# 28Pins_Schematic.net
KiCad netlist of a schematic drawn in Altium Designer
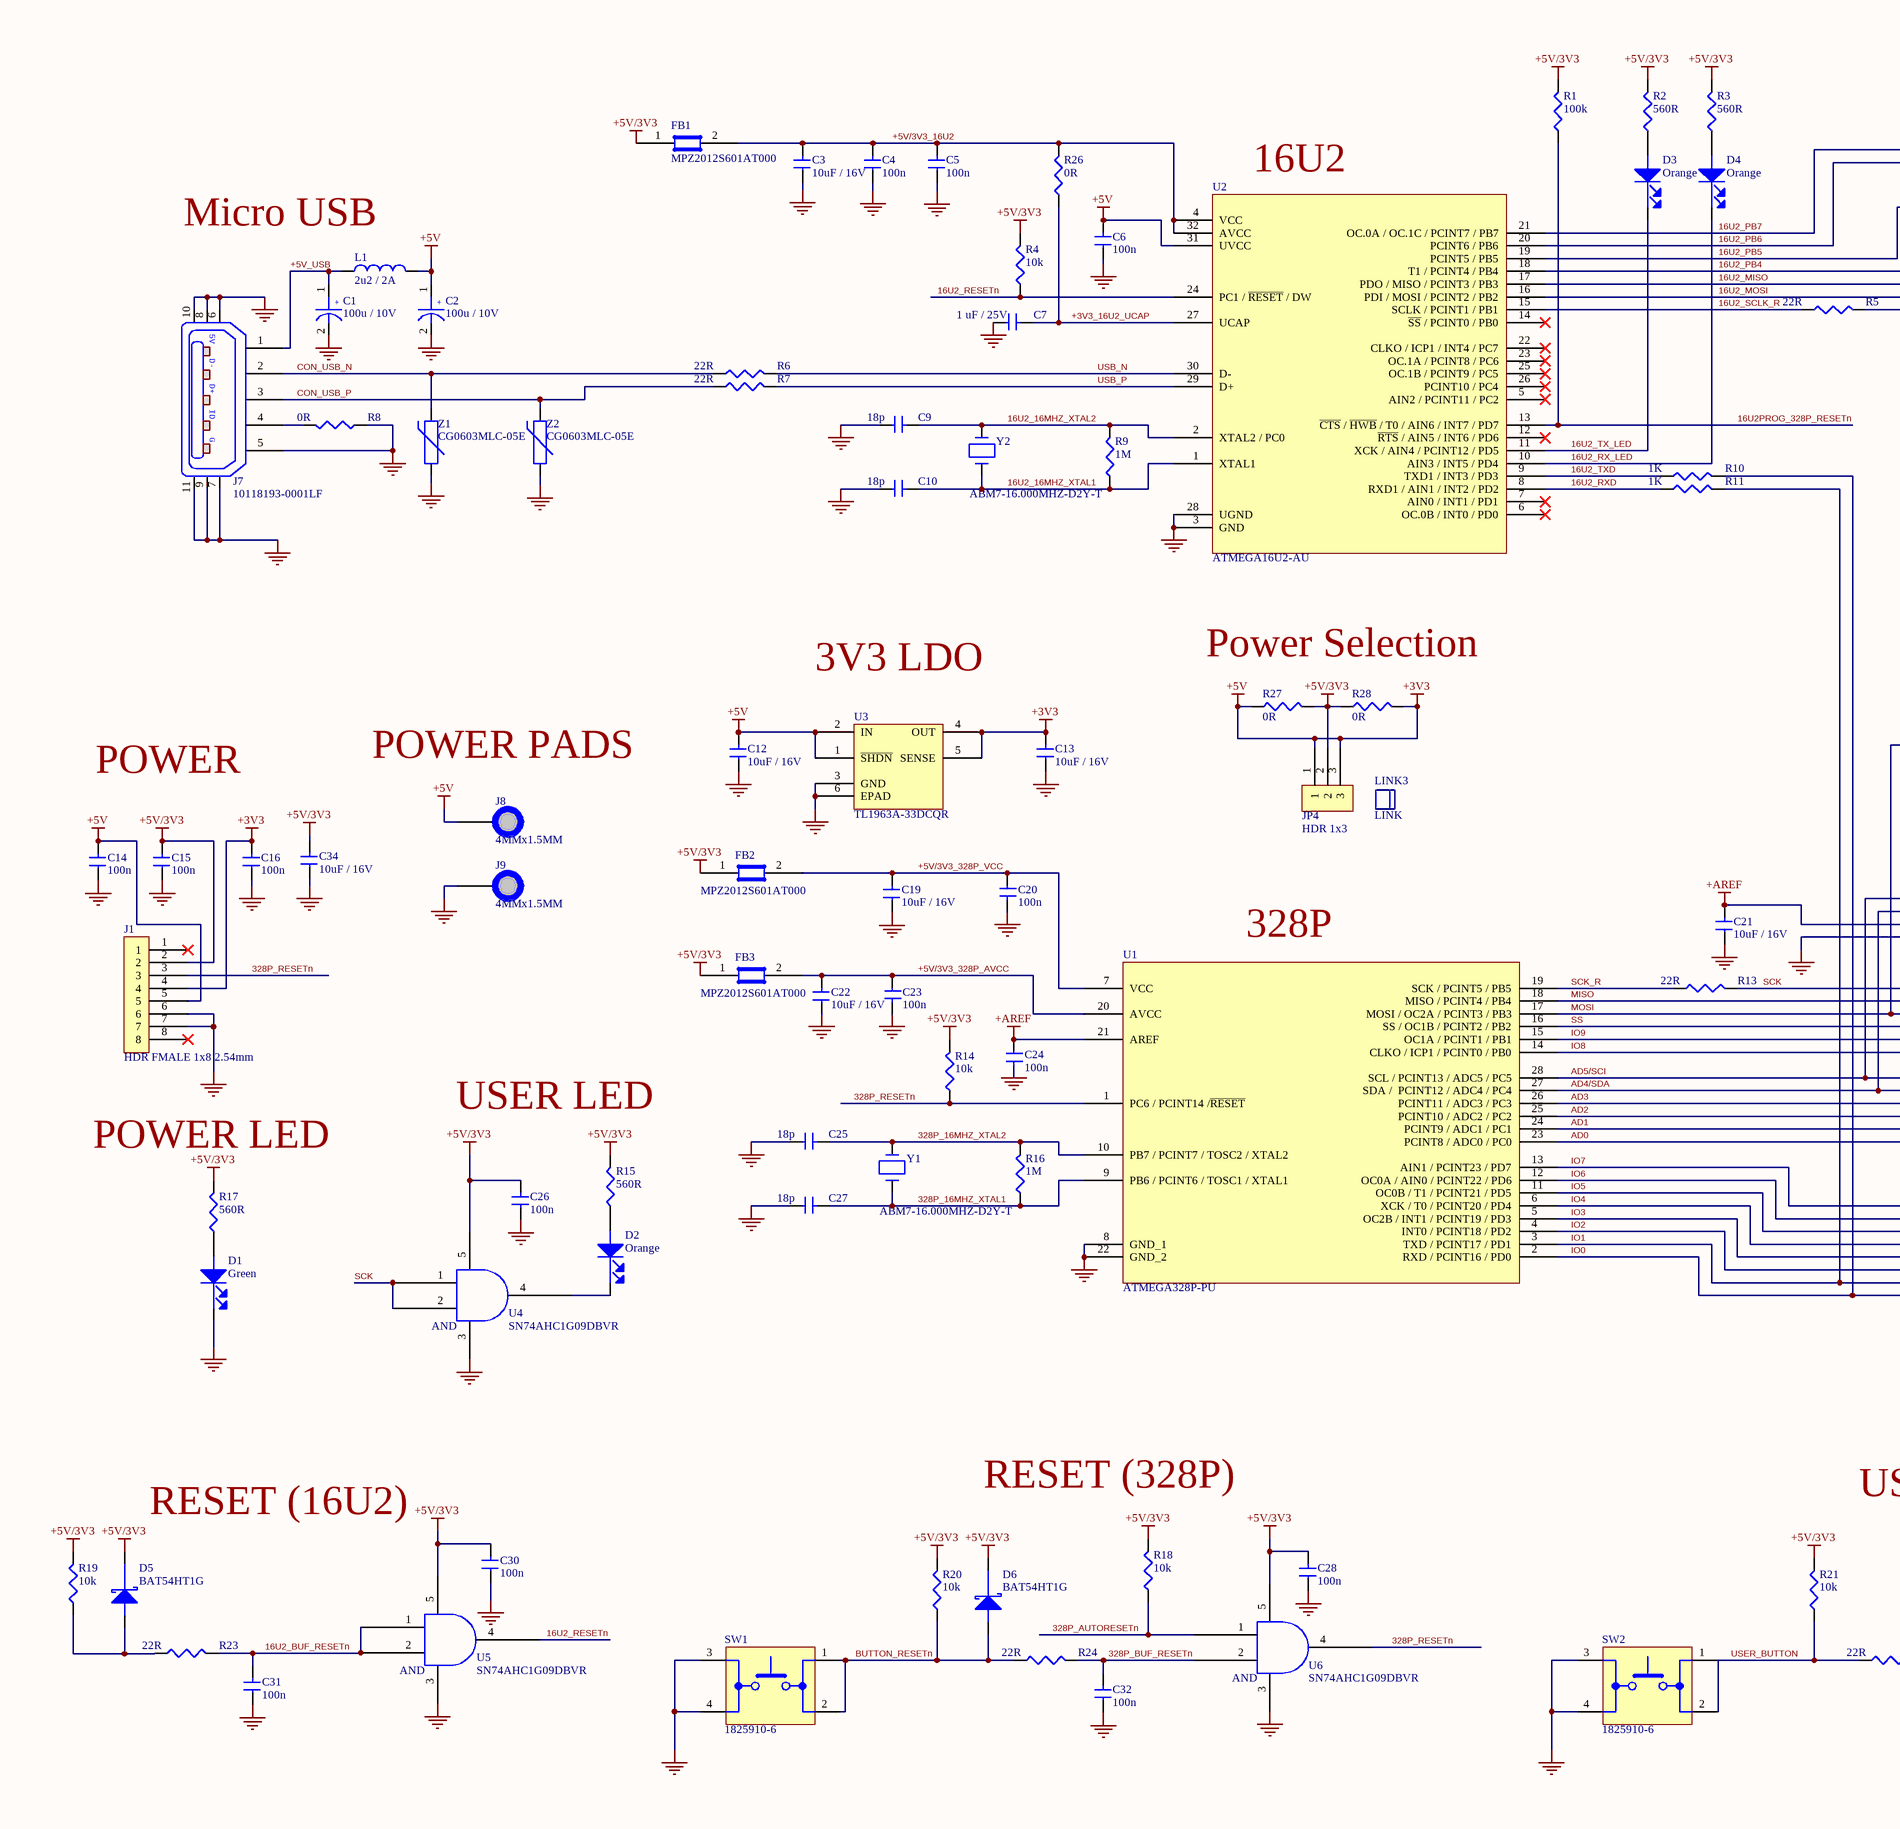
[diagram p0: 28Pins_Schematic.SchDoc, left]
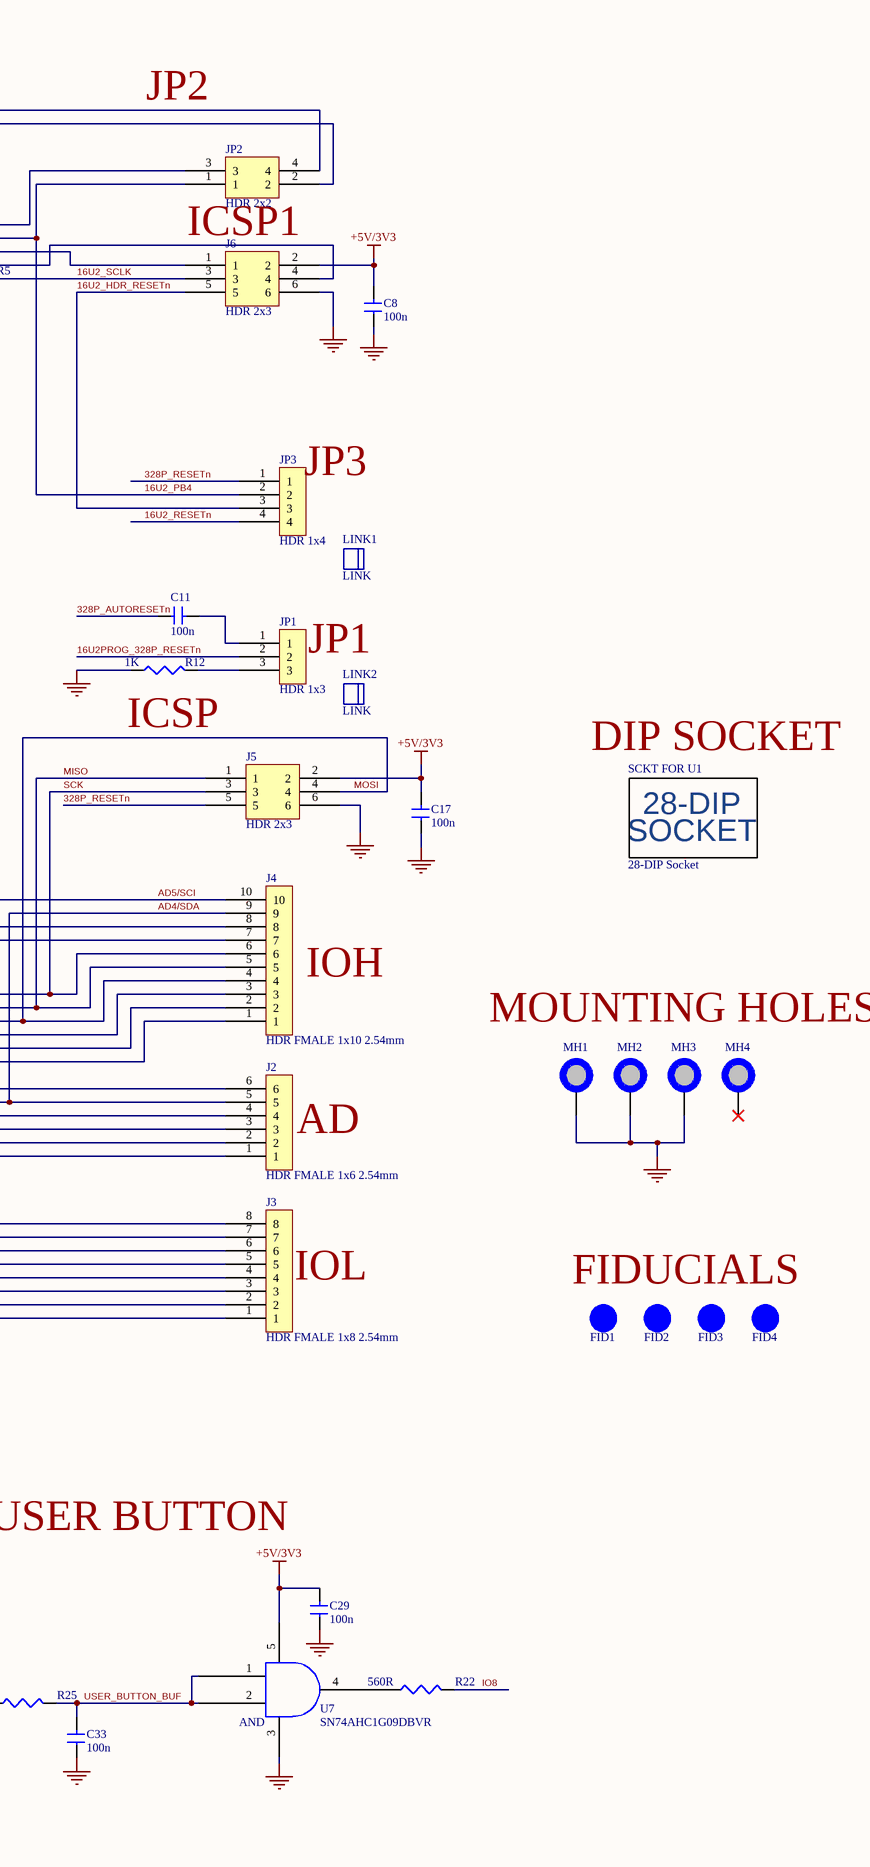
[diagram p1: 28Pins_Schematic.SchDoc, right]

(export (version "E")
  (design (tool "Eeschema 10.0.6"))
  (components
    (comp (ref "C1")
      (value "100u / 10V")
      (footprint "C_ALU_C_SIZE")
      (description "Cap Alum 100uF 10V 20% (5 X 5.4mm) SMD 50mA 1000 hr 85°C T/R")
      (fields
        (field (name "MANUFACTURER") "Panasonic")
        (field (name "MANUFACTURER PART NUMBER") "EEE-1AA101WR")
      )
      (libsource (lib "28Pins_Project_V1I1") (part "EEE-1AA101WR"))
    )
    (comp (ref "C2")
      (value "100u / 10V")
      (footprint "C_ALU_C_SIZE")
      (description "Cap Alum 100uF 10V 20% (5 X 5.4mm) SMD 50mA 1000 hr 85°C T/R")
      (fields
        (field (name "MANUFACTURER") "Panasonic")
        (field (name "MANUFACTURER PART NUMBER") "EEE-1AA101WR")
      )
      (libsource (lib "28Pins_Project_V1I1") (part "EEE-1AA101WR"))
    )
    (comp (ref "C3")
      (value "10uF / 16V")
      (footprint "C0805")
      (fields
        (field (name "MANUFACTURER") "TDK")
        (field (name "MANUFACTURER PART NUMBER") "C2012X5R1C106M125AC")
        (field (name "TOLERANCE") "20%")
      )
      (libsource (lib "28Pins_Project_V1I1") (part "C2012X5R1C106M125AC"))
    )
    (comp (ref "C4")
      (value "100n")
      (footprint "C0805")
      (fields
        (field (name "MANUFACTURER") "TDK")
        (field (name "MANUFACTURER PART NUMBER") "C2012X7R1H104K085AA")
        (field (name "TOLERANCE") "10%")
      )
      (libsource (lib "28Pins_Project_V1I1") (part "C2012X7R1H104K085AA"))
    )
    (comp (ref "C5")
      (value "100n")
      (footprint "C0805")
      (fields
        (field (name "MANUFACTURER") "TDK")
        (field (name "MANUFACTURER PART NUMBER") "C2012X7R1H104K085AA")
        (field (name "TOLERANCE") "10%")
      )
      (libsource (lib "28Pins_Project_V1I1") (part "C2012X7R1H104K085AA"))
    )
    (comp (ref "C6")
      (value "100n")
      (footprint "C0805")
      (fields
        (field (name "MANUFACTURER") "TDK")
        (field (name "MANUFACTURER PART NUMBER") "C2012X7R1H104K085AA")
        (field (name "TOLERANCE") "10%")
      )
      (libsource (lib "28Pins_Project_V1I1") (part "C2012X7R1H104K085AA"))
    )
    (comp (ref "C7")
      (value "1 uF / 25V")
      (footprint "C0805")
      (fields
        (field (name "MANUFACTURER") "TDK")
        (field (name "MANUFACTURER PART NUMBER") "C2012X5R1E105K125AA")
        (field (name "TOLERANCE") "10%")
      )
      (libsource (lib "28Pins_Project_V1I1") (part "C2012X5R1E105K125AA"))
    )
    (comp (ref "C8")
      (value "100n")
      (footprint "C0805")
      (fields
        (field (name "MANUFACTURER") "TDK")
        (field (name "MANUFACTURER PART NUMBER") "C2012X7R1H104K085AA")
        (field (name "TOLERANCE") "10%")
      )
      (libsource (lib "28Pins_Project_V1I1") (part "C2012X7R1H104K085AA"))
    )
    (comp (ref "C9")
      (value "18p")
      (footprint "C0805")
      (description "CAP CER 18PF 50V C0G/NP0 0805")
      (fields
        (field (name "MANUFACTURER") "KEMET")
        (field (name "MANUFACTURER PART NUMBER") "C0805C180J5GACTU")
      )
      (libsource (lib "28Pins_Project_V1I1") (part "C0805C180J5GACTU"))
    )
    (comp (ref "C10")
      (value "18p")
      (footprint "C0805")
      (description "CAP CER 18PF 50V C0G/NP0 0805")
      (fields
        (field (name "MANUFACTURER") "KEMET")
        (field (name "MANUFACTURER PART NUMBER") "C0805C180J5GACTU")
      )
      (libsource (lib "28Pins_Project_V1I1") (part "C0805C180J5GACTU"))
    )
    (comp (ref "C11")
      (value "100n")
      (footprint "C0805")
      (fields
        (field (name "MANUFACTURER") "TDK")
        (field (name "MANUFACTURER PART NUMBER") "C2012X7R1H104K085AA")
        (field (name "TOLERANCE") "10%")
      )
      (libsource (lib "28Pins_Project_V1I1") (part "C2012X7R1H104K085AA"))
    )
    (comp (ref "C12")
      (value "10uF / 16V")
      (footprint "C0805")
      (fields
        (field (name "MANUFACTURER") "TDK")
        (field (name "MANUFACTURER PART NUMBER") "C2012X5R1C106M125AC")
        (field (name "TOLERANCE") "20%")
      )
      (libsource (lib "28Pins_Project_V1I1") (part "C2012X5R1C106M125AC"))
    )
    (comp (ref "C13")
      (value "10uF / 16V")
      (footprint "C0805")
      (fields
        (field (name "MANUFACTURER") "TDK")
        (field (name "MANUFACTURER PART NUMBER") "C2012X5R1C106M125AC")
        (field (name "TOLERANCE") "20%")
      )
      (libsource (lib "28Pins_Project_V1I1") (part "C2012X5R1C106M125AC"))
    )
    (comp (ref "C14")
      (value "100n")
      (footprint "C0805")
      (fields
        (field (name "MANUFACTURER") "TDK")
        (field (name "MANUFACTURER PART NUMBER") "C2012X7R1H104K085AA")
        (field (name "TOLERANCE") "10%")
      )
      (libsource (lib "28Pins_Project_V1I1") (part "C2012X7R1H104K085AA"))
    )
    (comp (ref "C15")
      (value "100n")
      (footprint "C0805")
      (fields
        (field (name "MANUFACTURER") "TDK")
        (field (name "MANUFACTURER PART NUMBER") "C2012X7R1H104K085AA")
        (field (name "TOLERANCE") "10%")
      )
      (libsource (lib "28Pins_Project_V1I1") (part "C2012X7R1H104K085AA"))
    )
    (comp (ref "C16")
      (value "100n")
      (footprint "C0805")
      (fields
        (field (name "MANUFACTURER") "TDK")
        (field (name "MANUFACTURER PART NUMBER") "C2012X7R1H104K085AA")
        (field (name "TOLERANCE") "10%")
      )
      (libsource (lib "28Pins_Project_V1I1") (part "C2012X7R1H104K085AA"))
    )
    (comp (ref "C17")
      (value "100n")
      (footprint "C0805")
      (fields
        (field (name "MANUFACTURER") "TDK")
        (field (name "MANUFACTURER PART NUMBER") "C2012X7R1H104K085AA")
        (field (name "TOLERANCE") "10%")
      )
      (libsource (lib "28Pins_Project_V1I1") (part "C2012X7R1H104K085AA"))
    )
    (comp (ref "C19")
      (value "10uF / 16V")
      (footprint "C0805")
      (fields
        (field (name "MANUFACTURER") "TDK")
        (field (name "MANUFACTURER PART NUMBER") "C2012X5R1C106M125AC")
        (field (name "TOLERANCE") "20%")
      )
      (libsource (lib "28Pins_Project_V1I1") (part "C2012X5R1C106M125AC"))
    )
    (comp (ref "C20")
      (value "100n")
      (footprint "C0805")
      (fields
        (field (name "MANUFACTURER") "TDK")
        (field (name "MANUFACTURER PART NUMBER") "C2012X7R1H104K085AA")
        (field (name "TOLERANCE") "10%")
      )
      (libsource (lib "28Pins_Project_V1I1") (part "C2012X7R1H104K085AA"))
    )
    (comp (ref "C21")
      (value "10uF / 16V")
      (footprint "C0805")
      (fields
        (field (name "MANUFACTURER") "TDK")
        (field (name "MANUFACTURER PART NUMBER") "C2012X5R1C106M125AC")
        (field (name "TOLERANCE") "20%")
      )
      (libsource (lib "28Pins_Project_V1I1") (part "C2012X5R1C106M125AC"))
    )
    (comp (ref "C22")
      (value "10uF / 16V")
      (footprint "C0805")
      (fields
        (field (name "MANUFACTURER") "TDK")
        (field (name "MANUFACTURER PART NUMBER") "C2012X5R1C106M125AC")
        (field (name "TOLERANCE") "20%")
      )
      (libsource (lib "28Pins_Project_V1I1") (part "C2012X5R1C106M125AC"))
    )
    (comp (ref "C23")
      (value "100n")
      (footprint "C0805")
      (fields
        (field (name "MANUFACTURER") "TDK")
        (field (name "MANUFACTURER PART NUMBER") "C2012X7R1H104K085AA")
        (field (name "TOLERANCE") "10%")
      )
      (libsource (lib "28Pins_Project_V1I1") (part "C2012X7R1H104K085AA"))
    )
    (comp (ref "C24")
      (value "100n")
      (footprint "C0805")
      (fields
        (field (name "MANUFACTURER") "TDK")
        (field (name "MANUFACTURER PART NUMBER") "C2012X7R1H104K085AA")
        (field (name "TOLERANCE") "10%")
      )
      (libsource (lib "28Pins_Project_V1I1") (part "C2012X7R1H104K085AA"))
    )
    (comp (ref "C25")
      (value "18p")
      (footprint "C0805")
      (description "CAP CER 18PF 50V C0G/NP0 0805")
      (fields
        (field (name "MANUFACTURER") "KEMET")
        (field (name "MANUFACTURER PART NUMBER") "C0805C180J5GACTU")
      )
      (libsource (lib "28Pins_Project_V1I1") (part "C0805C180J5GACTU"))
    )
    (comp (ref "C26")
      (value "100n")
      (footprint "C0805")
      (fields
        (field (name "MANUFACTURER") "TDK")
        (field (name "MANUFACTURER PART NUMBER") "C2012X7R1H104K085AA")
        (field (name "TOLERANCE") "10%")
      )
      (libsource (lib "28Pins_Project_V1I1") (part "C2012X7R1H104K085AA"))
    )
    (comp (ref "C27")
      (value "18p")
      (footprint "C0805")
      (description "CAP CER 18PF 50V C0G/NP0 0805")
      (fields
        (field (name "MANUFACTURER") "KEMET")
        (field (name "MANUFACTURER PART NUMBER") "C0805C180J5GACTU")
      )
      (libsource (lib "28Pins_Project_V1I1") (part "C0805C180J5GACTU"))
    )
    (comp (ref "C28")
      (value "100n")
      (footprint "C0805")
      (fields
        (field (name "MANUFACTURER") "TDK")
        (field (name "MANUFACTURER PART NUMBER") "C2012X7R1H104K085AA")
        (field (name "TOLERANCE") "10%")
      )
      (libsource (lib "28Pins_Project_V1I1") (part "C2012X7R1H104K085AA"))
    )
    (comp (ref "C29")
      (value "100n")
      (footprint "C0805")
      (fields
        (field (name "MANUFACTURER") "TDK")
        (field (name "MANUFACTURER PART NUMBER") "C2012X7R1H104K085AA")
        (field (name "TOLERANCE") "10%")
      )
      (libsource (lib "28Pins_Project_V1I1") (part "C2012X7R1H104K085AA"))
    )
    (comp (ref "C30")
      (value "100n")
      (footprint "C0805")
      (fields
        (field (name "MANUFACTURER") "TDK")
        (field (name "MANUFACTURER PART NUMBER") "C2012X7R1H104K085AA")
        (field (name "TOLERANCE") "10%")
      )
      (libsource (lib "28Pins_Project_V1I1") (part "C2012X7R1H104K085AA"))
    )
    (comp (ref "C31")
      (value "100n")
      (footprint "C0805")
      (fields
        (field (name "MANUFACTURER") "TDK")
        (field (name "MANUFACTURER PART NUMBER") "C2012X7R1H104K085AA")
        (field (name "TOLERANCE") "10%")
      )
      (libsource (lib "28Pins_Project_V1I1") (part "C2012X7R1H104K085AA"))
    )
    (comp (ref "C32")
      (value "100n")
      (footprint "C0805")
      (fields
        (field (name "MANUFACTURER") "TDK")
        (field (name "MANUFACTURER PART NUMBER") "C2012X7R1H104K085AA")
        (field (name "TOLERANCE") "10%")
      )
      (libsource (lib "28Pins_Project_V1I1") (part "C2012X7R1H104K085AA"))
    )
    (comp (ref "C33")
      (value "100n")
      (footprint "C0805")
      (fields
        (field (name "MANUFACTURER") "TDK")
        (field (name "MANUFACTURER PART NUMBER") "C2012X7R1H104K085AA")
        (field (name "TOLERANCE") "10%")
      )
      (libsource (lib "28Pins_Project_V1I1") (part "C2012X7R1H104K085AA"))
    )
    (comp (ref "C34")
      (value "10uF / 16V")
      (footprint "C0805")
      (fields
        (field (name "MANUFACTURER") "TDK")
        (field (name "MANUFACTURER PART NUMBER") "C2012X5R1C106M125AC")
        (field (name "TOLERANCE") "20%")
      )
      (libsource (lib "28Pins_Project_V1I1") (part "C2012X5R1C106M125AC"))
    )
    (comp (ref "D1")
      (value "Green")
      (footprint "LED_0603")
      (description "LED Green Uni-Color 572nm 2-Pin Chip 0603(1608Metric) T/R")
      (fields
        (field (name "MANUFACTURER") "Osram Opto")
        (field (name "MANUFACTURER PART NUMBER") "LGL29K-G2J1-24-Z")
      )
      (libsource (lib "28Pins_Project_V1I1") (part "LGL29K-G2J1-24-Z"))
    )
    (comp (ref "D2")
      (value "Orange")
      (footprint "LED_0603")
      (description "LED ORANGE SMART OSRAM - LO L29K-H2K1-24-Z - 0603")
      (fields
        (field (name "MANUFACTURER") "Osram Opto")
        (field (name "MANUFACTURER PART NUMBER") "LOL29K-H2K1-24-Z")
      )
      (libsource (lib "28Pins_Project_V1I1") (part "LOL29K-H2K1-24-Z"))
    )
    (comp (ref "D3")
      (value "Orange")
      (footprint "LED_0603")
      (description "LED ORANGE SMART OSRAM - LO L29K-H2K1-24-Z - 0603")
      (fields
        (field (name "MANUFACTURER") "Osram Opto")
        (field (name "MANUFACTURER PART NUMBER") "LOL29K-H2K1-24-Z")
      )
      (libsource (lib "28Pins_Project_V1I1") (part "LOL29K-H2K1-24-Z"))
    )
    (comp (ref "D4")
      (value "Orange")
      (footprint "LED_0603")
      (description "LED ORANGE SMART OSRAM - LO L29K-H2K1-24-Z - 0603")
      (fields
        (field (name "MANUFACTURER") "Osram Opto")
        (field (name "MANUFACTURER PART NUMBER") "LOL29K-H2K1-24-Z")
      )
      (libsource (lib "28Pins_Project_V1I1") (part "LOL29K-H2K1-24-Z"))
    )
    (comp (ref "D5")
      (value "BAT54HT1G")
      (footprint "SOD323")
      (description "Diode Schottky 30V 200 mA, 800 mV, 600 mA, 150 C ;RoHS Compliant: Yes")
      (fields (field (name "MANUFACTURER") "ON Semiconductor / Fairchild"))
      (libsource (lib "28Pins_Project_V1I1") (part "BAT54HT1G"))
    )
    (comp (ref "D6")
      (value "BAT54HT1G")
      (footprint "SOD323")
      (description "Diode Schottky 30V 200 mA, 800 mV, 600 mA, 150 C ;RoHS Compliant: Yes")
      (fields (field (name "MANUFACTURER") "ON Semiconductor / Fairchild"))
      (libsource (lib "28Pins_Project_V1I1") (part "BAT54HT1G"))
    )
    (comp (ref "FB1")
      (value "MPZ2012S601AT000")
      (footprint "C0805")
      (description "FERRITE BEAD 600 OHM 0805 1LN")
      (fields (field (name "MANUFACTURER") "TDK"))
      (libsource (lib "28Pins_Project_V1I1") (part "MPZ2012S601AT000"))
    )
    (comp (ref "FB2")
      (value "MPZ2012S601AT000")
      (footprint "C0805")
      (description "FERRITE BEAD 600 OHM 0805 1LN")
      (fields (field (name "MANUFACTURER") "TDK"))
      (libsource (lib "28Pins_Project_V1I1") (part "MPZ2012S601AT000"))
    )
    (comp (ref "FB3")
      (value "MPZ2012S601AT000")
      (footprint "C0805")
      (description "FERRITE BEAD 600 OHM 0805 1LN")
      (fields (field (name "MANUFACTURER") "TDK"))
      (libsource (lib "28Pins_Project_V1I1") (part "MPZ2012S601AT000"))
    )
    (comp (ref "FID1")
      (value "FID_1MMC")
      (footprint "FID_40X120D")
      (description "Fiducial 40mil Diameter 120mil Mask")
      (libsource (lib "28Pins_Project_V1I1") (part "FID_1MMC"))
    )
    (comp (ref "FID2")
      (value "FID_1MMC")
      (footprint "FID_40X120D")
      (description "Fiducial 40mil Diameter 120mil Mask")
      (libsource (lib "28Pins_Project_V1I1") (part "FID_1MMC"))
    )
    (comp (ref "FID3")
      (value "FID_1MMC")
      (footprint "FID_40X120D")
      (description "Fiducial 40mil Diameter 120mil Mask")
      (libsource (lib "28Pins_Project_V1I1") (part "FID_1MMC"))
    )
    (comp (ref "FID4")
      (value "FID_1MMC")
      (footprint "FID_40X120D")
      (description "Fiducial 40mil Diameter 120mil Mask")
      (libsource (lib "28Pins_Project_V1I1") (part "FID_1MMC"))
    )
    (comp (ref "J1")
      (value "HDR FMALE 1x8 2.54mm")
      (footprint "Hdr_Female_1x8_2.54mm")
      (description "8-WAY 2.54mm (0.1\") Pitch SIL Vertical PC Tail Socket Assembly, selective gold + tin, 8 contacts")
      (fields (field (name "MANUFACTURER") "Harwin") (field (name "MANUFACTURER PART NUMBER") "M20-7820842"))
      (libsource (lib "28Pins_Project_V1I1") (part "M20-7820842"))
    )
    (comp (ref "J2")
      (value "HDR FMALE 1x6 2.54mm")
      (footprint "Hdr_Female_1x6_2.54mm")
      (description "06-WAY SIL VERT SOCKET L/FREE")
      (fields (field (name "MANUFACTURER") "Harwin") (field (name "MANUFACTURER PART NUMBER") "M20-7820646"))
      (libsource (lib "28Pins_Project_V1I1") (part "M20-7820646"))
    )
    (comp (ref "J3")
      (value "HDR FMALE 1x8 2.54mm")
      (footprint "Hdr_Female_1x8_2.54mm")
      (description "2.54mm (0.1\") Pitch SIL Vertical PC Tail Socket Assembly, selective gold + tin, 8 contacts")
      (fields (field (name "MANUFACTURER") "Harwin") (field (name "MANUFACTURER PART NUMBER") "M20-7820842"))
      (libsource (lib "") (part "M20-7820842_1"))
    )
    (comp (ref "J4")
      (value "HDR FMALE 1x10 2.54mm")
      (footprint "Hdr_Female_1x10_2.54mm")
      (fields (field (name "MANUFACTURER") "Harwin") (field (name "MANUFACTURER PART NUMBER") "M20-7821046"))
      (libsource (lib "28Pins_Project_V1I1") (part "M20-7821046"))
    )
    (comp (ref "J5")
      (value "HDR 2x3")
      (footprint "HDR_2x3_2.54MM")
      (description "CONN HEADER 6POS .100 STR 30AU")
      (fields
        (field (name "MANUFACTURER") "Amphenol FCI")
        (field (name "MANUFACTURER PART NUMBER") "67997-106HLF")
      )
      (libsource (lib "28Pins_Project_V1I1") (part "67997-106HLF"))
    )
    (comp (ref "J6")
      (value "HDR 2x3")
      (footprint "HDR_2x3_2.54MM")
      (description "CONN HEADER 6POS .100 STR 30AU")
      (fields
        (field (name "MANUFACTURER") "Amphenol FCI")
        (field (name "MANUFACTURER PART NUMBER") "67997-106HLF")
      )
      (libsource (lib "28Pins_Project_V1I1") (part "67997-106HLF"))
    )
    (comp (ref "J7")
      (value "10118193-0001LF")
      (footprint "10118193")
      (description "CONN USB MICRO B RECPT SMT R/A")
      (fields (field (name "MANUFACTURER") "Amphenol FCI"))
      (libsource (lib "28Pins_Project_V1I1") (part "10118193-0001LF"))
    )
    (comp (ref "J8")
      (value "4MMx1.5MM")
      (footprint "PAD_WITH_HOLE_4MMx1.5MM")
      (description "Pad with a hole 4mm x 1.5mm")
      (libsource (lib "28Pins_Project_V1I1") (part "PAD_WITH_HOLE_4MMx1.5MM"))
    )
    (comp (ref "J9")
      (value "4MMx1.5MM")
      (footprint "PAD_WITH_HOLE_4MMx1.5MM")
      (description "Pad with a hole 4mm x 1.5mm")
      (libsource (lib "28Pins_Project_V1I1") (part "PAD_WITH_HOLE_4MMx1.5MM"))
    )
    (comp (ref "JP1")
      (value "HDR 1x3")
      (footprint "Hdr_1x3_2.54mm")
      (description "HDR 3 POS 2.54mm Conn Unshrouded Header Solder ST Thru-Hole Bulk")
      (fields
        (field (name "MANUFACTURER") "Amphenol FCI")
        (field (name "MANUFACTURER PART NUMBER") "68000-103HLF")
      )
      (libsource (lib "") (part "68000-103HLF_1"))
    )
    (comp (ref "JP2")
      (value "HDR 2x2")
      (footprint "HDR_2x2_2.54MM")
      (description "CONN HEADER 4POS 2.54MM")
      (fields
        (field (name "MANUFACTURER") "Amphenol FCI")
        (field (name "MANUFACTURER PART NUMBER") "68602-204HLF")
      )
      (libsource (lib "28Pins_Project_V1I1") (part "68602-204HLF"))
    )
    (comp (ref "JP3")
      (value "HDR 1x4")
      (footprint "HDR_1x4_2.54MM")
      (description "CONN HEADER 4POS 2.54MM")
      (fields
        (field (name "MANUFACTURER") "Amphenol FCI")
        (field (name "MANUFACTURER PART NUMBER") "68001-204HLF")
      )
      (libsource (lib "28Pins_Project_V1I1") (part "68001-204HLF"))
    )
    (comp (ref "JP4")
      (value "HDR 1x3")
      (footprint "Hdr_1x3_2.54mm")
      (description "Conn HDR 3 POS 2.54mm  Unshrouded Header Solder ST Thru-Hole Bulk")
      (fields
        (field (name "MANUFACTURER") "Amphenol FCI")
        (field (name "MANUFACTURER PART NUMBER") "68000-103HLF")
      )
      (libsource (lib "28Pins_Project_V1I1") (part "68000-103HLF"))
    )
    (comp (ref "L1")
      (value "2u2 / 2A")
      (footprint "C1210_IND")
      (description "FIXED IND 2.2UH 2A 80 MOHM SMD")
      (fields
        (field (name "MANUFACTURER") "KEMET")
        (field (name "MANUFACTURER PART NUMBER") "L1210R2R2MDWIT")
      )
      (libsource (lib "28Pins_Project_V1I1") (part "L1210R2R2MDWIT"))
    )
    (comp (ref "LINK1")
      (value "LINK")
      (description "CONN JUMPER SHORTING .100\" GOLD")
      (fields
        (field (name "MANUFACTURER") "Sullins")
        (field (name "MANUFACTURER PART NUMBER") "QPC02SXGN-RC")
      )
      (libsource (lib "28Pins_Project_V1I1") (part "QPC02SXGN-RC"))
    )
    (comp (ref "LINK2")
      (value "LINK")
      (description "CONN JUMPER SHORTING .100\" GOLD")
      (fields
        (field (name "MANUFACTURER") "Sullins")
        (field (name "MANUFACTURER PART NUMBER") "QPC02SXGN-RC")
      )
      (libsource (lib "28Pins_Project_V1I1") (part "QPC02SXGN-RC"))
    )
    (comp (ref "LINK3")
      (value "LINK")
      (description "CONN JUMPER SHORTING .100\" GOLD")
      (fields
        (field (name "MANUFACTURER") "Sullins")
        (field (name "MANUFACTURER PART NUMBER") "QPC02SXGN-RC")
      )
      (libsource (lib "28Pins_Project_V1I1") (part "QPC02SXGN-RC"))
    )
    (comp (ref "MH1")
      (value "MH_7.4MMC_3.2MMD")
      (footprint "MH_7.4MMD_3_2MMD")
      (description "Mounting Hole 7.4mm Diameter, 3.xmm Drill")
      (libsource (lib "28Pins_Project_V1I1") (part "MH_7.4MMC_3.2"))
    )
    (comp (ref "MH2")
      (value "MH_7.4MMC_3.2MMD")
      (footprint "MH_7.4MMD_3_2MMD")
      (description "Mounting Hole 7.4mm Diameter, 3.xmm Drill")
      (libsource (lib "28Pins_Project_V1I1") (part "MH_7.4MMC_3.2"))
    )
    (comp (ref "MH3")
      (value "MH_7.4MMC_3.2MMD")
      (footprint "MH_7.4MMD_3_2MMD")
      (description "Mounting Hole 7.4mm Diameter, 3.xmm Drill")
      (libsource (lib "28Pins_Project_V1I1") (part "MH_7.4MMC_3.2"))
    )
    (comp (ref "MH4")
      (value "MH_7.4MMNC_3.2MMD")
      (footprint "MH_7.4MMD_3.2MMD_NON_COPPER_NPTH")
      (description "Hole 7.4mm Diameter (Non Copper) 3.2mm Drill NPTH")
      (libsource (lib "28Pins_Project_V1I1") (part "MH_7.4MMNC_3.2MMD"))
    )
    (comp (ref "R1")
      (value "100k")
      (footprint "R0805")
      (description "RES SMD 100K OHM YAGEO RC0805FR-07100KL RES, THICK FILM, 100K, 1%, 0.125W, 0805, REEL")
      (fields
        (field (name "MANUFACTURER") "Yageo")
        (field (name "MANUFACTURER PART NUMBER") "RC0805FR-07100KL")
      )
      (libsource (lib "28Pins_Project_V1I1") (part "RC0805FR-07100KL"))
    )
    (comp (ref "R2")
      (value "560R")
      (footprint "R0805")
      (description "RES SMD 560 OHM Surface Mount Thick Film, RC Series, 125 mW, - 1%, 150 V, 0805 [2012 Metric]")
      (fields
        (field (name "MANUFACTURER") "Yageo")
        (field (name "MANUFACTURER PART NUMBER") "RC0805FR-07560RL")
      )
      (libsource (lib "28Pins_Project_V1I1") (part "RC0805FR-07560RL"))
    )
    (comp (ref "R3")
      (value "560R")
      (footprint "R0805")
      (description "RES SMD 560 OHM Surface Mount Thick Film, RC Series, 125 mW, - 1%, 150 V, 0805 [2012 Metric]")
      (fields
        (field (name "MANUFACTURER") "Yageo")
        (field (name "MANUFACTURER PART NUMBER") "RC0805FR-07560RL")
      )
      (libsource (lib "28Pins_Project_V1I1") (part "RC0805FR-07560RL"))
    )
    (comp (ref "R4")
      (value "10k")
      (description "RES SMD 10K OHM 1% 1/8W 0805")
      (fields
        (field (name "MANUFACTURER") "Yageo")
        (field (name "MANUFACTURER PART NUMBER") "RC0805FR-0710KL")
      )
      (libsource (lib "28Pins_Project_V1I1") (part "RC0805FR-0710KL"))
    )
    (comp (ref "R5")
      (value "22R")
      (footprint "R0805")
      (description "RES SMD 22 OHM 1% 1/8W 0805")
      (fields
        (field (name "MANUFACTURER") "Yageo")
        (field (name "MANUFACTURER PART NUMBER") "RC0805FR-0722RL")
      )
      (libsource (lib "28Pins_Project_V1I1") (part "RC0805FR-0722RL"))
    )
    (comp (ref "R6")
      (value "22R")
      (footprint "R0805")
      (description "RES SMD 22 OHM 1% 1/8W 0805")
      (fields
        (field (name "MANUFACTURER") "Yageo")
        (field (name "MANUFACTURER PART NUMBER") "RC0805FR-0722RL")
      )
      (libsource (lib "28Pins_Project_V1I1") (part "RC0805FR-0722RL"))
    )
    (comp (ref "R7")
      (value "22R")
      (footprint "R0805")
      (description "RES SMD 22 OHM 1% 1/8W 0805")
      (fields
        (field (name "MANUFACTURER") "Yageo")
        (field (name "MANUFACTURER PART NUMBER") "RC0805FR-0722RL")
      )
      (libsource (lib "28Pins_Project_V1I1") (part "RC0805FR-0722RL"))
    )
    (comp (ref "R8")
      (value "0R")
      (footprint "R0805")
      (fields
        (field (name "MANUFACTURER") "Yageo")
        (field (name "MANUFACTURER PART NUMBER") "RC0805JR-070RL")
        (field (name "TOLERANCE") "5%")
      )
      (libsource (lib "28Pins_Project_V1I1") (part "RC0805JR-070RL"))
    )
    (comp (ref "R9")
      (value "1M")
      (footprint "R0805")
      (description "RES SMD 1M OHM 1% 1/8W 0805")
      (fields
        (field (name "MANUFACTURER") "Yageo")
        (field (name "MANUFACTURER PART NUMBER") "RC0805FR-071ML")
      )
      (libsource (lib "28Pins_Project_V1I1") (part "RC0805FR-071ML"))
    )
    (comp (ref "R10")
      (value "1K")
      (footprint "R0805")
      (fields
        (field (name "MANUFACTURER") "Yageo")
        (field (name "MANUFACTURER PART NUMBER") "RC0805FR-071KL")
        (field (name "TOLERANCE") "1%")
      )
      (libsource (lib "28Pins_Project_V1I1") (part "RC0805FR-071KL"))
    )
    (comp (ref "R11")
      (value "1K")
      (footprint "R0805")
      (fields
        (field (name "MANUFACTURER") "Yageo")
        (field (name "MANUFACTURER PART NUMBER") "RC0805FR-071KL")
        (field (name "TOLERANCE") "1%")
      )
      (libsource (lib "28Pins_Project_V1I1") (part "RC0805FR-071KL"))
    )
    (comp (ref "R12")
      (value "1K")
      (footprint "R0805")
      (fields
        (field (name "MANUFACTURER") "Yageo")
        (field (name "MANUFACTURER PART NUMBER") "RC0805FR-071KL")
        (field (name "TOLERANCE") "1%")
      )
      (libsource (lib "28Pins_Project_V1I1") (part "RC0805FR-071KL"))
    )
    (comp (ref "R13")
      (value "22R")
      (footprint "R0805")
      (description "RES SMD 22 OHM 1% 1/8W 0805")
      (fields
        (field (name "MANUFACTURER") "Yageo")
        (field (name "MANUFACTURER PART NUMBER") "RC0805FR-0722RL")
      )
      (libsource (lib "28Pins_Project_V1I1") (part "RC0805FR-0722RL"))
    )
    (comp (ref "R14")
      (value "10k")
      (description "RES SMD 10K OHM 1% 1/8W 0805")
      (fields
        (field (name "MANUFACTURER") "Yageo")
        (field (name "MANUFACTURER PART NUMBER") "RC0805FR-0710KL")
      )
      (libsource (lib "28Pins_Project_V1I1") (part "RC0805FR-0710KL"))
    )
    (comp (ref "R15")
      (value "560R")
      (footprint "R0805")
      (description "RES SMD 560 OHM Surface Mount Thick Film, RC Series, 125 mW, - 1%, 150 V, 0805 [2012 Metric]")
      (fields
        (field (name "MANUFACTURER") "Yageo")
        (field (name "MANUFACTURER PART NUMBER") "RC0805FR-07560RL")
      )
      (libsource (lib "28Pins_Project_V1I1") (part "RC0805FR-07560RL"))
    )
    (comp (ref "R16")
      (value "1M")
      (footprint "R0805")
      (description "RES SMD 1M OHM 1% 1/8W 0805")
      (fields
        (field (name "MANUFACTURER") "Yageo")
        (field (name "MANUFACTURER PART NUMBER") "RC0805FR-071ML")
      )
      (libsource (lib "28Pins_Project_V1I1") (part "RC0805FR-071ML"))
    )
    (comp (ref "R17")
      (value "560R")
      (footprint "R0805")
      (description "RES SMD 560 OHM Surface Mount Thick Film, RC Series, 125 mW, - 1%, 150 V, 0805 [2012 Metric]")
      (fields
        (field (name "MANUFACTURER") "Yageo")
        (field (name "MANUFACTURER PART NUMBER") "RC0805FR-07560RL")
      )
      (libsource (lib "28Pins_Project_V1I1") (part "RC0805FR-07560RL"))
    )
    (comp (ref "R18")
      (value "10k")
      (description "RES SMD 10K OHM 1% 1/8W 0805")
      (fields
        (field (name "MANUFACTURER") "Yageo")
        (field (name "MANUFACTURER PART NUMBER") "RC0805FR-0710KL")
      )
      (libsource (lib "28Pins_Project_V1I1") (part "RC0805FR-0710KL"))
    )
    (comp (ref "R19")
      (value "10k")
      (description "RES SMD 10K OHM 1% 1/8W 0805")
      (fields
        (field (name "MANUFACTURER") "Yageo")
        (field (name "MANUFACTURER PART NUMBER") "RC0805FR-0710KL")
      )
      (libsource (lib "28Pins_Project_V1I1") (part "RC0805FR-0710KL"))
    )
    (comp (ref "R20")
      (value "10k")
      (description "RES SMD 10K OHM 1% 1/8W 0805")
      (fields
        (field (name "MANUFACTURER") "Yageo")
        (field (name "MANUFACTURER PART NUMBER") "RC0805FR-0710KL")
      )
      (libsource (lib "28Pins_Project_V1I1") (part "RC0805FR-0710KL"))
    )
    (comp (ref "R21")
      (value "10k")
      (description "RES SMD 10K OHM 1% 1/8W 0805")
      (fields
        (field (name "MANUFACTURER") "Yageo")
        (field (name "MANUFACTURER PART NUMBER") "RC0805FR-0710KL")
      )
      (libsource (lib "28Pins_Project_V1I1") (part "RC0805FR-0710KL"))
    )
    (comp (ref "R22")
      (value "560R")
      (footprint "R0805")
      (description "RES SMD 560 OHM Surface Mount Thick Film, RC Series, 125 mW, - 1%, 150 V, 0805 [2012 Metric]")
      (fields
        (field (name "MANUFACTURER") "Yageo")
        (field (name "MANUFACTURER PART NUMBER") "RC0805FR-07560RL")
      )
      (libsource (lib "28Pins_Project_V1I1") (part "RC0805FR-07560RL"))
    )
    (comp (ref "R23")
      (value "22R")
      (footprint "R0805")
      (description "RES SMD 22 OHM 1% 1/8W 0805")
      (fields
        (field (name "MANUFACTURER") "Yageo")
        (field (name "MANUFACTURER PART NUMBER") "RC0805FR-0722RL")
      )
      (libsource (lib "28Pins_Project_V1I1") (part "RC0805FR-0722RL"))
    )
    (comp (ref "R24")
      (value "22R")
      (footprint "R0805")
      (description "RES SMD 22 OHM 1% 1/8W 0805")
      (fields
        (field (name "MANUFACTURER") "Yageo")
        (field (name "MANUFACTURER PART NUMBER") "RC0805FR-0722RL")
      )
      (libsource (lib "28Pins_Project_V1I1") (part "RC0805FR-0722RL"))
    )
    (comp (ref "R25")
      (value "22R")
      (footprint "R0805")
      (description "RES SMD 22 OHM 1% 1/8W 0805")
      (fields
        (field (name "MANUFACTURER") "Yageo")
        (field (name "MANUFACTURER PART NUMBER") "RC0805FR-0722RL")
      )
      (libsource (lib "28Pins_Project_V1I1") (part "RC0805FR-0722RL"))
    )
    (comp (ref "R26")
      (value "0R")
      (footprint "R0805")
      (fields
        (field (name "MANUFACTURER") "Yageo")
        (field (name "MANUFACTURER PART NUMBER") "RC0805JR-070RL")
        (field (name "TOLERANCE") "5%")
      )
      (libsource (lib "28Pins_Project_V1I1") (part "RC0805JR-070RL"))
    )
    (comp (ref "R27")
      (value "0R")
      (footprint "R0805")
      (fields
        (field (name "MANUFACTURER") "Yageo")
        (field (name "MANUFACTURER PART NUMBER") "RC0805JR-070RL")
        (field (name "TOLERANCE") "5%")
      )
      (libsource (lib "28Pins_Project_V1I1") (part "RC0805JR-070RL"))
    )
    (comp (ref "R28")
      (value "0R")
      (footprint "R0805")
      (fields
        (field (name "MANUFACTURER") "Yageo")
        (field (name "MANUFACTURER PART NUMBER") "RC0805JR-070RL")
        (field (name "TOLERANCE") "5%")
      )
      (libsource (lib "28Pins_Project_V1I1") (part "RC0805JR-070RL"))
    )
    (comp (ref "SCKT FOR U1")
      (value "28-DIP Socket")
      (footprint "28_DIP_7.62mm_SOCKET")
      (description "CONN IC DIP SOCKET 28POS TIN")
      (fields (field (name "MANUFACTURER") "3M") (field (name "MANUFACTURER PART NUMBER") "4828-3004-CP"))
      (libsource (lib "28Pins_Project_V1I1") (part "4828-3004-CP"))
    )
    (comp (ref "SW1")
      (value "1825910-6")
      (footprint "1825910-6")
      (description "SWITCH TACTILE SPST-NO 0.05A 24V")
      (fields (field (name "MANUFACTURER") "TE Connectivity Alcoswitch"))
      (libsource (lib "28Pins_Project_V1I1") (part "1825910-6"))
    )
    (comp (ref "SW2")
      (value "1825910-6")
      (footprint "1825910-6")
      (description "SWITCH TACTILE SPST-NO 0.05A 24V")
      (fields (field (name "MANUFACTURER") "TE Connectivity Alcoswitch"))
      (libsource (lib "28Pins_Project_V1I1") (part "1825910-6"))
    )
    (comp (ref "U1")
      (value "ATMEGA328P-PU")
      (footprint "28_DIP_7.62mm - duplicate")
      (description "ATMEGA328P-PU; 8 bit Microcontroller AVR 20MHz 1; 32kb Flash; 2kb RAM; I2C SPI 2")
      (fields (field (name "MANUFACTURER") "Microchip / Atmel"))
      (libsource (lib "28Pins_Project_V1I1") (part "ATMEGA328P-PU"))
    )
    (comp (ref "U2")
      (value "ATMEGA16U2-AU")
      (footprint "TQFP32")
      (description "MICROCHIP - ATMEGA16U2-AU - MCU, 8BIT, MEGAAVR, 16MHZ, TQFP-32")
      (fields (field (name "MANUFACTURER") "Microchip / Atmel"))
      (libsource (lib "28Pins_Project_V1I1") (part "ATMEGA16U2-AU"))
    )
    (comp (ref "U3")
      (value "TL1963A-33DCQR")
      (footprint "DCQ (R-PDSO-G6)")
      (description "IC REG LINEAR 3.3V 1.5A SOT223-6")
      (fields (field (name "MANUFACTURER") "Texas Instruments"))
      (libsource (lib "28Pins_Project_V1I1") (part "TL1963A-33DCQR"))
    )
    (comp (ref "U4")
      (value "SN74AHC1G09DBVR")
      (footprint "DBV_SOT_23_5")
      (description "AND Gate - TEXAS INSTRUMENTS - SN74AHC1G09DBVR, 74AHC1G09, 2 Input, 2 V to 5.5 V, SOT-23-5")
      (fields (field (name "MANUFACTURER") "Texas Instruments"))
      (libsource (lib "28Pins_Project_V1I1") (part "SN74AHC1G09DBVR"))
    )
    (comp (ref "U5")
      (value "SN74AHC1G09DBVR")
      (footprint "DBV_SOT_23_5")
      (description "AND Gate - TEXAS INSTRUMENTS - SN74AHC1G09DBVR, 74AHC1G09, 2 Input, 2 V to 5.5 V, SOT-23-5")
      (fields (field (name "MANUFACTURER") "Texas Instruments"))
      (libsource (lib "28Pins_Project_V1I1") (part "SN74AHC1G09DBVR"))
    )
    (comp (ref "U6")
      (value "SN74AHC1G09DBVR")
      (footprint "DBV_SOT_23_5")
      (description "AND Gate - TEXAS INSTRUMENTS - SN74AHC1G09DBVR, 74AHC1G09, 2 Input, 2 V to 5.5 V, SOT-23-5")
      (fields (field (name "MANUFACTURER") "Texas Instruments"))
      (libsource (lib "28Pins_Project_V1I1") (part "SN74AHC1G09DBVR"))
    )
    (comp (ref "U7")
      (value "SN74AHC1G09DBVR")
      (footprint "DBV_SOT_23_5")
      (description "AND Gate - TEXAS INSTRUMENTS - SN74AHC1G09DBVR, 74AHC1G09, 2 Input, 2 V to 5.5 V, SOT-23-5")
      (fields (field (name "MANUFACTURER") "Texas Instruments"))
      (libsource (lib "28Pins_Project_V1I1") (part "SN74AHC1G09DBVR"))
    )
    (comp (ref "Y1")
      (value "ABM7-16.000MHZ-D2Y-T")
      (footprint "ABM7_v1_1_BIG")
      (description "CRYSTAL 16.0000MHZ 18PF SMD")
      (fields (field (name "MANUFACTURER") "Abracon") (field (name "TOLERANCE") "20ppm"))
      (libsource (lib "28Pins_Project_V1I1") (part "ABM7-16.000MHZ-D2Y-T"))
    )
    (comp (ref "Y2")
      (value "ABM7-16.000MHZ-D2Y-T")
      (footprint "ABM7_v1_1_BIG")
      (description "CRYSTAL 16.0000MHZ 18PF SMD")
      (fields (field (name "MANUFACTURER") "Abracon") (field (name "TOLERANCE") "20ppm"))
      (libsource (lib "28Pins_Project_V1I1") (part "ABM7-16.000MHZ-D2Y-T"))
    )
    (comp (ref "Z1")
      (value "CG0603MLC-05E")
      (footprint "R0603")
      (description "VARISTOR 0603")
      (fields (field (name "MANUFACTURER") "Bourns") (field (name "VOLTAGE") "5V"))
      (libsource (lib "28Pins_Project_V1I1") (part "CG0603MLC-05E"))
    )
    (comp (ref "Z2")
      (value "CG0603MLC-05E")
      (footprint "R0603")
      (description "VARISTOR 0603")
      (fields (field (name "MANUFACTURER") "Bourns") (field (name "VOLTAGE") "5V"))
      (libsource (lib "28Pins_Project_V1I1") (part "CG0603MLC-05E"))
    )
  )
  (nets
    (net (code "1") (name "+3V3") (class "Default")
      (node (ref "C12") (pin "2") (pinfunction "2_2") (pintype "passive"))
      (node (ref "C13") (pin "2") (pinfunction "2_2") (pintype "passive"))
      (node (ref "C14") (pin "2") (pinfunction "2_2") (pintype "passive"))
      (node (ref "C16") (pin "2") (pinfunction "2_2") (pintype "passive"))
      (node (ref "C2") (pin "1") (pinfunction "1_1") (pintype "passive"))
      (node (ref "C6") (pin "2") (pinfunction "2_2") (pintype "passive"))
      (node (ref "J1") (pin "4") (pinfunction "4_4") (pintype "passive"))
      (node (ref "J1") (pin "5") (pinfunction "5_5") (pintype "passive"))
      (node (ref "J8") (pin "1") (pinfunction "1_1") (pintype "passive"))
      (node (ref "JP4") (pin "1") (pinfunction "1_1") (pintype "passive"))
      (node (ref "JP4") (pin "3") (pinfunction "3_3") (pintype "passive"))
      (node (ref "L1") (pin "2") (pinfunction "2_2") (pintype "passive"))
      (node (ref "R27") (pin "1") (pinfunction "1_1") (pintype "passive"))
      (node (ref "R28") (pin "2") (pinfunction "2_2") (pintype "passive"))
      (node (ref "U2") (pin "31") (pinfunction "UVCC_31") (pintype "passive"))
      (node (ref "U3") (pin "1") (pinfunction "~{SHDN}_1") (pintype "passive"))
      (node (ref "U3") (pin "2") (pinfunction "IN_2") (pintype "passive"))
      (node (ref "U3") (pin "4") (pinfunction "OUT_4") (pintype "passive"))
      (node (ref "U3") (pin "5") (pinfunction "SENSE_5") (pintype "passive"))
    )
    (net (code "2") (name "+5V{slash}3V3") (class "Default")
      (node (ref "C15") (pin "2") (pinfunction "2_2") (pintype "passive"))
      (node (ref "C17") (pin "2") (pinfunction "2_2") (pintype "passive"))
      (node (ref "C26") (pin "2") (pinfunction "2_2") (pintype "passive"))
      (node (ref "C28") (pin "2") (pinfunction "2_2") (pintype "passive"))
      (node (ref "C29") (pin "2") (pinfunction "2_2") (pintype "passive"))
      (node (ref "C30") (pin "2") (pinfunction "2_2") (pintype "passive"))
      (node (ref "C34") (pin "2") (pinfunction "2_2") (pintype "passive"))
      (node (ref "C8") (pin "2") (pinfunction "2_2") (pintype "passive"))
      (node (ref "D5") (pin "1") (pinfunction "Cathode_1") (pintype "passive"))
      (node (ref "D6") (pin "1") (pinfunction "Cathode_1") (pintype "passive"))
      (node (ref "FB1") (pin "1") (pinfunction "1_1") (pintype "passive"))
      (node (ref "FB2") (pin "1") (pinfunction "1_1") (pintype "passive"))
      (node (ref "FB3") (pin "1") (pinfunction "1_1") (pintype "passive"))
      (node (ref "J1") (pin "2") (pinfunction "2_2") (pintype "passive"))
      (node (ref "J5") (pin "2") (pinfunction "2_2") (pintype "passive"))
      (node (ref "J6") (pin "2") (pinfunction "2_2") (pintype "passive"))
      (node (ref "JP4") (pin "2") (pinfunction "2_2") (pintype "passive"))
      (node (ref "R1") (pin "2") (pinfunction "2_2") (pintype "passive"))
      (node (ref "R14") (pin "2") (pinfunction "2_2") (pintype "passive"))
      (node (ref "R15") (pin "2") (pinfunction "2_2") (pintype "passive"))
      (node (ref "R17") (pin "2") (pinfunction "2_2") (pintype "passive"))
      (node (ref "R18") (pin "2") (pinfunction "2_2") (pintype "passive"))
      (node (ref "R19") (pin "2") (pinfunction "2_2") (pintype "passive"))
      (node (ref "R2") (pin "2") (pinfunction "2_2") (pintype "passive"))
      (node (ref "R20") (pin "2") (pinfunction "2_2") (pintype "passive"))
      (node (ref "R21") (pin "2") (pinfunction "2_2") (pintype "passive"))
      (node (ref "R27") (pin "2") (pinfunction "2_2") (pintype "passive"))
      (node (ref "R28") (pin "1") (pinfunction "1_1") (pintype "passive"))
      (node (ref "R3") (pin "2") (pinfunction "2_2") (pintype "passive"))
      (node (ref "R4") (pin "2") (pinfunction "2_2") (pintype "passive"))
      (node (ref "U4") (pin "5") (pinfunction "5_5") (pintype "passive"))
      (node (ref "U5") (pin "5") (pinfunction "5_5") (pintype "passive"))
      (node (ref "U6") (pin "5") (pinfunction "5_5") (pintype "passive"))
      (node (ref "U7") (pin "5") (pinfunction "5_5") (pintype "passive"))
    )
    (net (code "3") (name "+AREF") (class "Default")
      (node (ref "C21") (pin "2") (pinfunction "2_2") (pintype "passive"))
      (node (ref "C24") (pin "1") (pinfunction "1_1") (pintype "passive"))
      (node (ref "J4") (pin "8") (pinfunction "8_8") (pintype "passive"))
      (node (ref "U1") (pin "21") (pinfunction "AREF_21") (pintype "passive"))
    )
    (net (code "4") (name "/+3V3_16U2_UCAP") (class "Default")
      (node (ref "C7") (pin "2") (pinfunction "2_2") (pintype "passive"))
      (node (ref "R26") (pin "1") (pinfunction "1_1") (pintype "passive"))
      (node (ref "U2") (pin "27") (pinfunction "UCAP_27") (pintype "passive"))
    )
    (net (code "5") (name "/+5V_USB") (class "Default")
      (node (ref "C1") (pin "1") (pinfunction "1_1") (pintype "passive"))
      (node (ref "J7") (pin "1") (pinfunction "1_1") (pintype "passive"))
      (node (ref "L1") (pin "1") (pinfunction "1_1") (pintype "passive"))
    )
    (net (code "6") (name "/+5V{slash}3V3_16U2") (class "Default")
      (node (ref "C3") (pin "2") (pinfunction "2_2") (pintype "passive"))
      (node (ref "C4") (pin "2") (pinfunction "2_2") (pintype "passive"))
      (node (ref "C5") (pin "2") (pinfunction "2_2") (pintype "passive"))
      (node (ref "FB1") (pin "2") (pinfunction "2_2") (pintype "passive"))
      (node (ref "R26") (pin "2") (pinfunction "2_2") (pintype "passive"))
      (node (ref "U2") (pin "32") (pinfunction "AVCC_32") (pintype "passive"))
      (node (ref "U2") (pin "4") (pinfunction "VCC_4") (pintype "passive"))
    )
    (net (code "7") (name "/+5V{slash}3V3_328P_AVCC") (class "Default")
      (node (ref "C22") (pin "2") (pinfunction "2_2") (pintype "passive"))
      (node (ref "C23") (pin "1") (pinfunction "1_1") (pintype "passive"))
      (node (ref "FB3") (pin "2") (pinfunction "2_2") (pintype "passive"))
      (node (ref "U1") (pin "20") (pinfunction "AVCC_20") (pintype "passive"))
    )
    (net (code "8") (name "/+5V{slash}3V3_328P_VCC") (class "Default")
      (node (ref "C19") (pin "2") (pinfunction "2_2") (pintype "passive"))
      (node (ref "C20") (pin "1") (pinfunction "1_1") (pintype "passive"))
      (node (ref "FB2") (pin "2") (pinfunction "2_2") (pintype "passive"))
      (node (ref "U1") (pin "7") (pinfunction "VCC_7") (pintype "passive"))
    )
    (net (code "9") (name "/16U2PROG_328P_RESETn") (class "Default")
      (node (ref "JP1") (pin "2") (pinfunction "2_2") (pintype "passive"))
      (node (ref "R1") (pin "1") (pinfunction "1_1") (pintype "passive"))
      (node (ref "U2") (pin "13") (pinfunction "~{CTS}_/_~{HWB}_/_T0_/_AIN6_/_INT7_/_PD7_13") (pintype "passive"))
    )
    (net (code "10") (name "/16U2_16MHZ_XTAL1") (class "Default")
      (node (ref "C10") (pin "2") (pinfunction "2_2") (pintype "passive"))
      (node (ref "R9") (pin "1") (pinfunction "1_1") (pintype "passive"))
      (node (ref "U2") (pin "1") (pinfunction "XTAL1_1") (pintype "passive"))
      (node (ref "Y2") (pin "1") (pinfunction "1_1") (pintype "passive"))
    )
    (net (code "11") (name "/16U2_16MHZ_XTAL2") (class "Default")
      (node (ref "C9") (pin "2") (pinfunction "2_2") (pintype "passive"))
      (node (ref "R9") (pin "2") (pinfunction "2_2") (pintype "passive"))
      (node (ref "U2") (pin "2") (pinfunction "XTAL2_/_PC0_2") (pintype "passive"))
      (node (ref "Y2") (pin "2") (pinfunction "2_2") (pintype "passive"))
    )
    (net (code "12") (name "/16U2_BUF_RESETn") (class "Default")
      (node (ref "C31") (pin "2") (pinfunction "2_2") (pintype "passive"))
      (node (ref "R23") (pin "2") (pinfunction "2_2") (pintype "passive"))
      (node (ref "U5") (pin "1") (pinfunction "1_1") (pintype "passive"))
      (node (ref "U5") (pin "2") (pinfunction "2_2") (pintype "passive"))
    )
    (net (code "13") (name "/16U2_HDR_RESETn") (class "Default")
      (node (ref "J6") (pin "5") (pinfunction "5_5") (pintype "passive"))
      (node (ref "JP3") (pin "3") (pinfunction "3_3") (pintype "passive"))
    )
    (net (code "14") (name "/16U2_MISO") (class "Default")
      (node (ref "J6") (pin "1") (pinfunction "1_1") (pintype "passive"))
      (node (ref "U2") (pin "17") (pinfunction "PDO_/_MISO_/_PCINT3_/_PB3_17") (pintype "passive"))
    )
    (net (code "15") (name "/16U2_MOSI") (class "Default")
      (node (ref "J6") (pin "4") (pinfunction "4_4") (pintype "passive"))
      (node (ref "U2") (pin "16") (pinfunction "PDI_/_MOSI_/_PCINT2_/_PB2_16") (pintype "passive"))
    )
    (net (code "16") (name "/16U2_PB4") (class "Default")
      (node (ref "JP2") (pin "1") (pinfunction "1_1") (pintype "passive"))
      (node (ref "JP3") (pin "2") (pinfunction "2_2") (pintype "passive"))
      (node (ref "U2") (pin "18") (pinfunction "T1_/_PCINT4_/_PB4_18") (pintype "passive"))
    )
    (net (code "17") (name "/16U2_PB5") (class "Default")
      (node (ref "JP2") (pin "3") (pinfunction "3_3") (pintype "passive"))
      (node (ref "U2") (pin "19") (pinfunction "PCINT5_/_PB5_19") (pintype "passive"))
    )
    (net (code "18") (name "/16U2_PB6") (class "Default")
      (node (ref "JP2") (pin "2") (pinfunction "2_2") (pintype "passive"))
      (node (ref "U2") (pin "20") (pinfunction "PCINT6_/_PB6_20") (pintype "passive"))
    )
    (net (code "19") (name "/16U2_PB7") (class "Default")
      (node (ref "JP2") (pin "4") (pinfunction "4_4") (pintype "passive"))
      (node (ref "U2") (pin "21") (pinfunction "OC.0A_/_OC.1C_/_PCINT7_/_PB7_21") (pintype "passive"))
    )
    (net (code "20") (name "/16U2_RESETn") (class "Default")
      (node (ref "JP3") (pin "4") (pinfunction "4_4") (pintype "passive"))
      (node (ref "R4") (pin "1") (pinfunction "1_1") (pintype "passive"))
      (node (ref "U2") (pin "24") (pinfunction "PC1_/_~{RESET}_/_DW_24") (pintype "passive"))
      (node (ref "U5") (pin "4") (pinfunction "4_4") (pintype "passive"))
    )
    (net (code "21") (name "/16U2_RXD") (class "Default")
      (node (ref "R11") (pin "1") (pinfunction "1_1") (pintype "passive"))
      (node (ref "U2") (pin "8") (pinfunction "RXD1_/_AIN1_/_INT2_/_PD2_8") (pintype "passive"))
    )
    (net (code "22") (name "/16U2_RX_LED") (class "Default")
      (node (ref "D4") (pin "1") (pinfunction "Cathode_1") (pintype "passive"))
      (node (ref "U2") (pin "10") (pinfunction "AIN3_/_INT5_/_PD4_10") (pintype "passive"))
    )
    (net (code "23") (name "/16U2_SCLK") (class "Default")
      (node (ref "J6") (pin "3") (pinfunction "3_3") (pintype "passive"))
      (node (ref "R5") (pin "2") (pinfunction "2_2") (pintype "passive"))
    )
    (net (code "24") (name "/16U2_SCLK_R") (class "Default")
      (node (ref "R5") (pin "1") (pinfunction "1_1") (pintype "passive"))
      (node (ref "U2") (pin "15") (pinfunction "SCLK_/_PCINT1_/_PB1_15") (pintype "passive"))
    )
    (net (code "25") (name "/16U2_TXD") (class "Default")
      (node (ref "R10") (pin "1") (pinfunction "1_1") (pintype "passive"))
      (node (ref "U2") (pin "9") (pinfunction "TXD1_/_INT3_/_PD3_9") (pintype "passive"))
    )
    (net (code "26") (name "/16U2_TX_LED") (class "Default")
      (node (ref "D3") (pin "1") (pinfunction "Cathode_1") (pintype "passive"))
      (node (ref "U2") (pin "11") (pinfunction "XCK_/_AIN4_/_PCINT12_/_PD5_11") (pintype "passive"))
    )
    (net (code "27") (name "/328P_16MHZ_XTAL1") (class "Default")
      (node (ref "C27") (pin "2") (pinfunction "2_2") (pintype "passive"))
      (node (ref "R16") (pin "1") (pinfunction "1_1") (pintype "passive"))
      (node (ref "U1") (pin "9") (pinfunction "PB6_/_PCINT6_/_TOSC1_/_XTAL1_9") (pintype "passive"))
      (node (ref "Y1") (pin "1") (pinfunction "1_1") (pintype "passive"))
    )
    (net (code "28") (name "/328P_16MHZ_XTAL2") (class "Default")
      (node (ref "C25") (pin "2") (pinfunction "2_2") (pintype "passive"))
      (node (ref "R16") (pin "2") (pinfunction "2_2") (pintype "passive"))
      (node (ref "U1") (pin "10") (pinfunction "PB7_/_PCINT7_/_TOSC2_/_XTAL2_10") (pintype "passive"))
      (node (ref "Y1") (pin "2") (pinfunction "2_2") (pintype "passive"))
    )
    (net (code "29") (name "/328P_AUTORESETn") (class "Default")
      (node (ref "C11") (pin "1") (pinfunction "1_1") (pintype "passive"))
      (node (ref "R18") (pin "1") (pinfunction "1_1") (pintype "passive"))
      (node (ref "U6") (pin "1") (pinfunction "1_1") (pintype "passive"))
    )
    (net (code "30") (name "/328P_BUF_RESETn") (class "Default")
      (node (ref "C32") (pin "2") (pinfunction "2_2") (pintype "passive"))
      (node (ref "R24") (pin "2") (pinfunction "2_2") (pintype "passive"))
      (node (ref "U6") (pin "2") (pinfunction "2_2") (pintype "passive"))
    )
    (net (code "31") (name "/328P_RESETn") (class "Default")
      (node (ref "J1") (pin "3") (pinfunction "3_3") (pintype "passive"))
      (node (ref "J5") (pin "5") (pinfunction "5_5") (pintype "passive"))
      (node (ref "JP3") (pin "1") (pinfunction "1_1") (pintype "passive"))
      (node (ref "R14") (pin "1") (pinfunction "1_1") (pintype "passive"))
      (node (ref "U1") (pin "1") (pinfunction "PC6_/_PCINT14_/~{RESET}_1") (pintype "passive"))
      (node (ref "U6") (pin "4") (pinfunction "4_4") (pintype "passive"))
    )
    (net (code "32") (name "/AD0") (class "Default")
      (node (ref "J2") (pin "1") (pinfunction "1_1") (pintype "passive"))
      (node (ref "U1") (pin "23") (pinfunction "PCINT8_/_ADC0_/_PC0_23") (pintype "passive"))
    )
    (net (code "33") (name "/AD1") (class "Default")
      (node (ref "J2") (pin "2") (pinfunction "2_2") (pintype "passive"))
      (node (ref "U1") (pin "24") (pinfunction "PCINT9_/_ADC1_/_PC1_24") (pintype "passive"))
    )
    (net (code "34") (name "/AD2") (class "Default")
      (node (ref "J2") (pin "3") (pinfunction "3_3") (pintype "passive"))
      (node (ref "U1") (pin "25") (pinfunction "PCINT10_/_ADC2_/_PC2_25") (pintype "passive"))
    )
    (net (code "35") (name "/AD3") (class "Default")
      (node (ref "J2") (pin "4") (pinfunction "4_4") (pintype "passive"))
      (node (ref "U1") (pin "26") (pinfunction "PCINT11_/_ADC3_/_PC3_26") (pintype "passive"))
    )
    (net (code "36") (name "/AD4{slash}SDA") (class "Default")
      (node (ref "J2") (pin "5") (pinfunction "5_5") (pintype "passive"))
      (node (ref "J4") (pin "9") (pinfunction "9_9") (pintype "passive"))
      (node (ref "U1") (pin "27") (pinfunction "SDA_/__PCINT12_/_ADC4_/_PC4_27") (pintype "passive"))
    )
    (net (code "37") (name "/AD5{slash}SCI") (class "Default")
      (node (ref "J2") (pin "6") (pinfunction "6_6") (pintype "passive"))
      (node (ref "J4") (pin "10") (pinfunction "10_10") (pintype "passive"))
      (node (ref "U1") (pin "28") (pinfunction "SCL_/_PCINT13_/_ADC5_/_PC5_28") (pintype "passive"))
    )
    (net (code "38") (name "/BUTTON_RESETn") (class "Default")
      (node (ref "D6") (pin "2") (pinfunction "Anode_2") (pintype "passive"))
      (node (ref "R20") (pin "1") (pinfunction "1_1") (pintype "passive"))
      (node (ref "R24") (pin "1") (pinfunction "1_1") (pintype "passive"))
    )
    (net (code "39") (name "/CON_USB_N") (class "Default")
      (node (ref "J7") (pin "2") (pinfunction "2_2") (pintype "passive"))
      (node (ref "R6") (pin "1") (pinfunction "1_1") (pintype "passive"))
      (node (ref "Z1") (pin "2") (pinfunction "2_2") (pintype "passive"))
    )
    (net (code "40") (name "/CON_USB_P") (class "Default")
      (node (ref "J7") (pin "3") (pinfunction "3_3") (pintype "passive"))
      (node (ref "R7") (pin "1") (pinfunction "1_1") (pintype "passive"))
      (node (ref "Z2") (pin "2") (pinfunction "2_2") (pintype "passive"))
    )
    (net (code "41") (name "/IO0") (class "Default")
      (node (ref "J3") (pin "1") (pinfunction "1_1") (pintype "passive"))
      (node (ref "R10") (pin "2") (pinfunction "2_2") (pintype "passive"))
      (node (ref "U1") (pin "2") (pinfunction "RXD_/_PCINT16_/_PD0_2") (pintype "passive"))
    )
    (net (code "42") (name "/IO1") (class "Default")
      (node (ref "J3") (pin "2") (pinfunction "2_2") (pintype "passive"))
      (node (ref "R11") (pin "2") (pinfunction "2_2") (pintype "passive"))
      (node (ref "U1") (pin "3") (pinfunction "TXD_/_PCINT17_/_PD1_3") (pintype "passive"))
    )
    (net (code "43") (name "/IO2") (class "Default")
      (node (ref "J3") (pin "3") (pinfunction "3_3") (pintype "passive"))
      (node (ref "U1") (pin "4") (pinfunction "INT0_/_PCINT18_/_PD2_4") (pintype "passive"))
    )
    (net (code "44") (name "/IO3") (class "Default")
      (node (ref "J3") (pin "4") (pinfunction "4_4") (pintype "passive"))
      (node (ref "U1") (pin "5") (pinfunction "OC2B_/_INT1_/_PCINT19_/_PD3_5") (pintype "passive"))
    )
    (net (code "45") (name "/IO4") (class "Default")
      (node (ref "J3") (pin "5") (pinfunction "5_5") (pintype "passive"))
      (node (ref "U1") (pin "6") (pinfunction "XCK_/_T0_/_PCINT20_/_PD4_6") (pintype "passive"))
    )
    (net (code "46") (name "/IO5") (class "Default")
      (node (ref "J3") (pin "6") (pinfunction "6_6") (pintype "passive"))
      (node (ref "U1") (pin "11") (pinfunction "OC0B_/_T1_/_PCINT21_/_PD5_11") (pintype "passive"))
    )
    (net (code "47") (name "/IO6") (class "Default")
      (node (ref "J3") (pin "7") (pinfunction "7_7") (pintype "passive"))
      (node (ref "U1") (pin "12") (pinfunction "OC0A_/_AIN0_/_PCINT22_/_PD6_12") (pintype "passive"))
    )
    (net (code "48") (name "/IO7") (class "Default")
      (node (ref "J3") (pin "8") (pinfunction "8_8") (pintype "passive"))
      (node (ref "U1") (pin "13") (pinfunction "AIN1_/_PCINT23_/_PD7_13") (pintype "passive"))
    )
    (net (code "49") (name "/IO8") (class "Default")
      (node (ref "J4") (pin "1") (pinfunction "1_1") (pintype "passive"))
      (node (ref "R22") (pin "2") (pinfunction "2_2") (pintype "passive"))
      (node (ref "U1") (pin "14") (pinfunction "CLKO_/_ICP1_/_PCINT0_/_PB0_14") (pintype "passive"))
    )
    (net (code "50") (name "/IO9") (class "Default")
      (node (ref "J4") (pin "2") (pinfunction "2_2") (pintype "passive"))
      (node (ref "U1") (pin "15") (pinfunction "OC1A_/_PCINT1_/_PB1_15") (pintype "passive"))
    )
    (net (code "51") (name "/MISO") (class "Default")
      (node (ref "J4") (pin "5") (pinfunction "5_5") (pintype "passive"))
      (node (ref "J5") (pin "1") (pinfunction "1_1") (pintype "passive"))
      (node (ref "U1") (pin "18") (pinfunction "MISO_/_PCINT4_/_PB4_18") (pintype "passive"))
    )
    (net (code "52") (name "/MOSI") (class "Default")
      (node (ref "J4") (pin "4") (pinfunction "4_4") (pintype "passive"))
      (node (ref "J5") (pin "4") (pinfunction "4_4") (pintype "passive"))
      (node (ref "U1") (pin "17") (pinfunction "MOSI_/_OC2A_/_PCINT3_/_PB3_17") (pintype "passive"))
    )
    (net (code "53") (name "/SCK") (class "Default")
      (node (ref "J4") (pin "6") (pinfunction "6_6") (pintype "passive"))
      (node (ref "J5") (pin "3") (pinfunction "3_3") (pintype "passive"))
      (node (ref "R13") (pin "2") (pinfunction "2_2") (pintype "passive"))
      (node (ref "U4") (pin "1") (pinfunction "1_1") (pintype "passive"))
      (node (ref "U4") (pin "2") (pinfunction "2_2") (pintype "passive"))
    )
    (net (code "54") (name "/SCK_R") (class "Default")
      (node (ref "R13") (pin "1") (pinfunction "1_1") (pintype "passive"))
      (node (ref "U1") (pin "19") (pinfunction "SCK_/_PCINT5_/_PB5_19") (pintype "passive"))
    )
    (net (code "55") (name "/SS") (class "Default")
      (node (ref "J4") (pin "3") (pinfunction "3_3") (pintype "passive"))
      (node (ref "U1") (pin "16") (pinfunction "SS_/_OC1B_/_PCINT2_/_PB2_16") (pintype "passive"))
    )
    (net (code "56") (name "/USB_N") (class "Default")
      (node (ref "R6") (pin "2") (pinfunction "2_2") (pintype "passive"))
      (node (ref "U2") (pin "30") (pinfunction "D-_30") (pintype "passive"))
    )
    (net (code "57") (name "/USB_P") (class "Default")
      (node (ref "R7") (pin "2") (pinfunction "2_2") (pintype "passive"))
      (node (ref "U2") (pin "29") (pinfunction "D+_29") (pintype "passive"))
    )
    (net (code "58") (name "/USER_BUTTON") (class "Default")
      (node (ref "R21") (pin "1") (pinfunction "1_1") (pintype "passive"))
      (node (ref "R25") (pin "1") (pinfunction "1_1") (pintype "passive"))
    )
    (net (code "59") (name "/USER_BUTTON_BUF") (class "Default")
      (node (ref "C33") (pin "2") (pinfunction "2_2") (pintype "passive"))
      (node (ref "R25") (pin "2") (pinfunction "2_2") (pintype "passive"))
      (node (ref "U7") (pin "1") (pinfunction "1_1") (pintype "passive"))
      (node (ref "U7") (pin "2") (pinfunction "2_2") (pintype "passive"))
    )
    (net (code "60") (name "<NO NET>") (class "Default")
      (node (ref "C14") (pin "1") (pinfunction "1_1") (pintype "passive"))
      (node (ref "C15") (pin "1") (pinfunction "1_1") (pintype "passive"))
      (node (ref "C16") (pin "1") (pinfunction "1_1") (pintype "passive"))
      (node (ref "C34") (pin "1") (pinfunction "1_1") (pintype "passive"))
      (node (ref "D1") (pin "1") (pinfunction "Cathode_1") (pintype "passive"))
      (node (ref "J1") (pin "6") (pinfunction "6_6") (pintype "passive"))
      (node (ref "J1") (pin "7") (pinfunction "7_7") (pintype "passive"))
      (node (ref "J9") (pin "1") (pinfunction "1_1") (pintype "passive"))
    )
    (net (code "61") (name "GND") (class "Default")
      (node (ref "C1") (pin "2") (pinfunction "2_2") (pintype "passive"))
      (node (ref "C10") (pin "1") (pinfunction "1_1") (pintype "passive"))
      (node (ref "C12") (pin "1") (pinfunction "1_1") (pintype "passive"))
      (node (ref "C13") (pin "1") (pinfunction "1_1") (pintype "passive"))
      (node (ref "C17") (pin "1") (pinfunction "1_1") (pintype "passive"))
      (node (ref "C19") (pin "1") (pinfunction "1_1") (pintype "passive"))
      (node (ref "C2") (pin "2") (pinfunction "2_2") (pintype "passive"))
      (node (ref "C20") (pin "2") (pinfunction "2_2") (pintype "passive"))
      (node (ref "C21") (pin "1") (pinfunction "1_1") (pintype "passive"))
      (node (ref "C22") (pin "1") (pinfunction "1_1") (pintype "passive"))
      (node (ref "C23") (pin "2") (pinfunction "2_2") (pintype "passive"))
      (node (ref "C24") (pin "2") (pinfunction "2_2") (pintype "passive"))
      (node (ref "C25") (pin "1") (pinfunction "1_1") (pintype "passive"))
      (node (ref "C26") (pin "1") (pinfunction "1_1") (pintype "passive"))
      (node (ref "C27") (pin "1") (pinfunction "1_1") (pintype "passive"))
      (node (ref "C28") (pin "1") (pinfunction "1_1") (pintype "passive"))
      (node (ref "C29") (pin "1") (pinfunction "1_1") (pintype "passive"))
      (node (ref "C3") (pin "1") (pinfunction "1_1") (pintype "passive"))
      (node (ref "C30") (pin "1") (pinfunction "1_1") (pintype "passive"))
      (node (ref "C31") (pin "1") (pinfunction "1_1") (pintype "passive"))
      (node (ref "C32") (pin "1") (pinfunction "1_1") (pintype "passive"))
      (node (ref "C33") (pin "1") (pinfunction "1_1") (pintype "passive"))
      (node (ref "C4") (pin "1") (pinfunction "1_1") (pintype "passive"))
      (node (ref "C5") (pin "1") (pinfunction "1_1") (pintype "passive"))
      (node (ref "C6") (pin "1") (pinfunction "1_1") (pintype "passive"))
      (node (ref "C7") (pin "1") (pinfunction "1_1") (pintype "passive"))
      (node (ref "C8") (pin "1") (pinfunction "1_1") (pintype "passive"))
      (node (ref "C9") (pin "1") (pinfunction "1_1") (pintype "passive"))
      (node (ref "J4") (pin "7") (pinfunction "7_7") (pintype "passive"))
      (node (ref "J5") (pin "6") (pinfunction "6_6") (pintype "passive"))
      (node (ref "J6") (pin "6") (pinfunction "6_6") (pintype "passive"))
      (node (ref "J7") (pin "10") (pinfunction "10_10") (pintype "passive"))
      (node (ref "J7") (pin "11") (pinfunction "11_11") (pintype "passive"))
      (node (ref "J7") (pin "5") (pinfunction "5_5") (pintype "passive"))
      (node (ref "J7") (pin "6") (pinfunction "6_6") (pintype "passive"))
      (node (ref "J7") (pin "7") (pinfunction "7_7") (pintype "passive"))
      (node (ref "J7") (pin "8") (pinfunction "8_8") (pintype "passive"))
      (node (ref "J7") (pin "9") (pinfunction "9_9") (pintype "passive"))
      (node (ref "MH1") (pin "1") (pinfunction "1_1") (pintype "passive"))
      (node (ref "MH2") (pin "1") (pinfunction "1_1") (pintype "passive"))
      (node (ref "MH3") (pin "1") (pinfunction "1_1") (pintype "passive"))
      (node (ref "R12") (pin "1") (pinfunction "1_1") (pintype "passive"))
      (node (ref "R8") (pin "1") (pinfunction "1_1") (pintype "passive"))
      (node (ref "SW1") (pin "3") (pinfunction "3_3") (pintype "passive"))
      (node (ref "SW1") (pin "4") (pinfunction "4_4") (pintype "passive"))
      (node (ref "SW2") (pin "3") (pinfunction "3_3") (pintype "passive"))
      (node (ref "SW2") (pin "4") (pinfunction "4_4") (pintype "passive"))
      (node (ref "U1") (pin "22") (pinfunction "GND_2_22") (pintype "passive"))
      (node (ref "U1") (pin "8") (pinfunction "GND_1_8") (pintype "passive"))
      (node (ref "U2") (pin "28") (pinfunction "UGND_28") (pintype "passive"))
      (node (ref "U2") (pin "3") (pinfunction "GND_3") (pintype "passive"))
      (node (ref "U3") (pin "3") (pinfunction "GND_3") (pintype "passive"))
      (node (ref "U3") (pin "6") (pinfunction "EPAD_6") (pintype "passive"))
      (node (ref "U4") (pin "3") (pinfunction "3_3") (pintype "passive"))
      (node (ref "U5") (pin "3") (pinfunction "3_3") (pintype "passive"))
      (node (ref "U6") (pin "3") (pinfunction "3_3") (pintype "passive"))
      (node (ref "U7") (pin "3") (pinfunction "3_3") (pintype "passive"))
    )
    (net (code "62") (name "Net-(C11-Pad2)") (class "Default")
      (node (ref "C11") (pin "2") (pinfunction "2_2") (pintype "passive"))
      (node (ref "JP1") (pin "1") (pinfunction "1_1") (pintype "passive"))
    )
    (net (code "63") (name "Net-(D1-Anode)") (class "Default")
      (node (ref "D1") (pin "2") (pinfunction "Anode_2") (pintype "passive"))
      (node (ref "R17") (pin "1") (pinfunction "1_1") (pintype "passive"))
    )
    (net (code "64") (name "Net-(D2-Anode)") (class "Default")
      (node (ref "D2") (pin "2") (pinfunction "Anode_2") (pintype "passive"))
      (node (ref "R15") (pin "1") (pinfunction "1_1") (pintype "passive"))
    )
    (net (code "65") (name "Net-(D2-Cathode)") (class "Default")
      (node (ref "D2") (pin "1") (pinfunction "Cathode_1") (pintype "passive"))
      (node (ref "U4") (pin "4") (pinfunction "4_4") (pintype "passive"))
    )
    (net (code "66") (name "Net-(D3-Anode)") (class "Default")
      (node (ref "D3") (pin "2") (pinfunction "Anode_2") (pintype "passive"))
      (node (ref "R2") (pin "1") (pinfunction "1_1") (pintype "passive"))
    )
    (net (code "67") (name "Net-(D4-Anode)") (class "Default")
      (node (ref "D4") (pin "2") (pinfunction "Anode_2") (pintype "passive"))
      (node (ref "R3") (pin "1") (pinfunction "1_1") (pintype "passive"))
    )
    (net (code "68") (name "Net-(D5-Anode)") (class "Default")
      (node (ref "D5") (pin "2") (pinfunction "Anode_2") (pintype "passive"))
      (node (ref "R19") (pin "1") (pinfunction "1_1") (pintype "passive"))
      (node (ref "R23") (pin "1") (pinfunction "1_1") (pintype "passive"))
    )
    (net (code "69") (name "Net-(J7-Pad4)") (class "Default")
      (node (ref "J7") (pin "4") (pinfunction "4_4") (pintype "passive"))
      (node (ref "R8") (pin "2") (pinfunction "2_2") (pintype "passive"))
    )
    (net (code "70") (name "Net-(JP1-Pad3)") (class "Default")
      (node (ref "JP1") (pin "3") (pinfunction "3_3") (pintype "passive"))
      (node (ref "R12") (pin "2") (pinfunction "2_2") (pintype "passive"))
    )
    (net (code "71") (name "Net-(R22-Pad1)") (class "Default")
      (node (ref "R22") (pin "1") (pinfunction "1_1") (pintype "passive"))
      (node (ref "U7") (pin "4") (pinfunction "4_4") (pintype "passive"))
    )
    (net (code "72") (name "unconnected-(J1-Pad1)") (class "Default")
      (node (ref "J1") (pin "1") (pinfunction "1_1") (pintype "passive+no_connect"))
    )
    (net (code "73") (name "unconnected-(J1-Pad8)") (class "Default")
      (node (ref "J1") (pin "8") (pinfunction "8_8") (pintype "passive+no_connect"))
    )
    (net (code "74") (name "unconnected-(MH4-Pad1)") (class "Default")
      (node (ref "MH4") (pin "1") (pinfunction "1_1") (pintype "passive+no_connect"))
    )
    (net (code "75") (name "unconnected-(SW1-Pad1)") (class "Default")
      (node (ref "SW1") (pin "1") (pinfunction "1_1") (pintype "passive"))
    )
    (net (code "76") (name "unconnected-(SW1-Pad2)") (class "Default")
      (node (ref "SW1") (pin "2") (pinfunction "2_2") (pintype "passive"))
    )
    (net (code "77") (name "unconnected-(SW2-Pad1)") (class "Default")
      (node (ref "SW2") (pin "1") (pinfunction "1_1") (pintype "passive"))
    )
    (net (code "78") (name "unconnected-(SW2-Pad2)") (class "Default")
      (node (ref "SW2") (pin "2") (pinfunction "2_2") (pintype "passive"))
    )
    (net (code "79") (name "unconnected-(U2-AIN0_{slash}_INT1_{slash}_PD1-Pad7)") (class "Default")
      (node (ref "U2") (pin "7") (pinfunction "AIN0_/_INT1_/_PD1_7") (pintype "passive+no_connect"))
    )
    (net (code "80") (name "unconnected-(U2-AIN2_{slash}_PCINT11_{slash}_PC2-Pad5)") (class "Default")
      (node (ref "U2") (pin "5") (pinfunction "AIN2_/_PCINT11_/_PC2_5") (pintype "passive+no_connect"))
    )
    (net (code "81") (name "unconnected-(U2-CLKO_{slash}_ICP1_{slash}_INT4_{slash}_PC7-Pad22)") (class "Default")
      (node (ref "U2") (pin "22") (pinfunction "CLKO_/_ICP1_/_INT4_/_PC7_22") (pintype "passive+no_connect"))
    )
    (net (code "82") (name "unconnected-(U2-OC.0B_{slash}_INT0_{slash}_PD0-Pad6)") (class "Default")
      (node (ref "U2") (pin "6") (pinfunction "OC.0B_/_INT0_/_PD0_6") (pintype "passive+no_connect"))
    )
    (net (code "83") (name "unconnected-(U2-OC.1A_{slash}_PCINT8_{slash}_PC6-Pad23)") (class "Default")
      (node (ref "U2") (pin "23") (pinfunction "OC.1A_/_PCINT8_/_PC6_23") (pintype "passive+no_connect"))
    )
    (net (code "84") (name "unconnected-(U2-OC.1B_{slash}_PCINT9_{slash}_PC5-Pad25)") (class "Default")
      (node (ref "U2") (pin "25") (pinfunction "OC.1B_/_PCINT9_/_PC5_25") (pintype "passive+no_connect"))
    )
    (net (code "85") (name "unconnected-(U2-PCINT10_{slash}_PC4-Pad26)") (class "Default")
      (node (ref "U2") (pin "26") (pinfunction "PCINT10_/_PC4_26") (pintype "passive+no_connect"))
    )
    (net (code "86") (name "unconnected-(U2-~{RTS}_{slash}_AIN5_{slash}_INT6_{slash}_PD6-Pad12)") (class "Default")
      (node (ref "U2") (pin "12") (pinfunction "~{RTS}_/_AIN5_/_INT6_/_PD6_12") (pintype "passive+no_connect"))
    )
    (net (code "87") (name "unconnected-(U2-~{SS}_{slash}_PCINT0_{slash}_PB0-Pad14)") (class "Default")
      (node (ref "U2") (pin "14") (pinfunction "~{SS}_/_PCINT0_/_PB0_14") (pintype "passive+no_connect"))
    )
    (net (code "88") (name "unconnected-(Z1-Pad1)") (class "Default")
      (node (ref "Z1") (pin "1") (pinfunction "1_1") (pintype "passive"))
    )
    (net (code "89") (name "unconnected-(Z2-Pad1)") (class "Default")
      (node (ref "Z2") (pin "1") (pinfunction "1_1") (pintype "passive"))
    )
  )
)
